# SCH_led_transistor_2026-04-28.net
KiCad netlist of a schematic drawn in EasyEDA
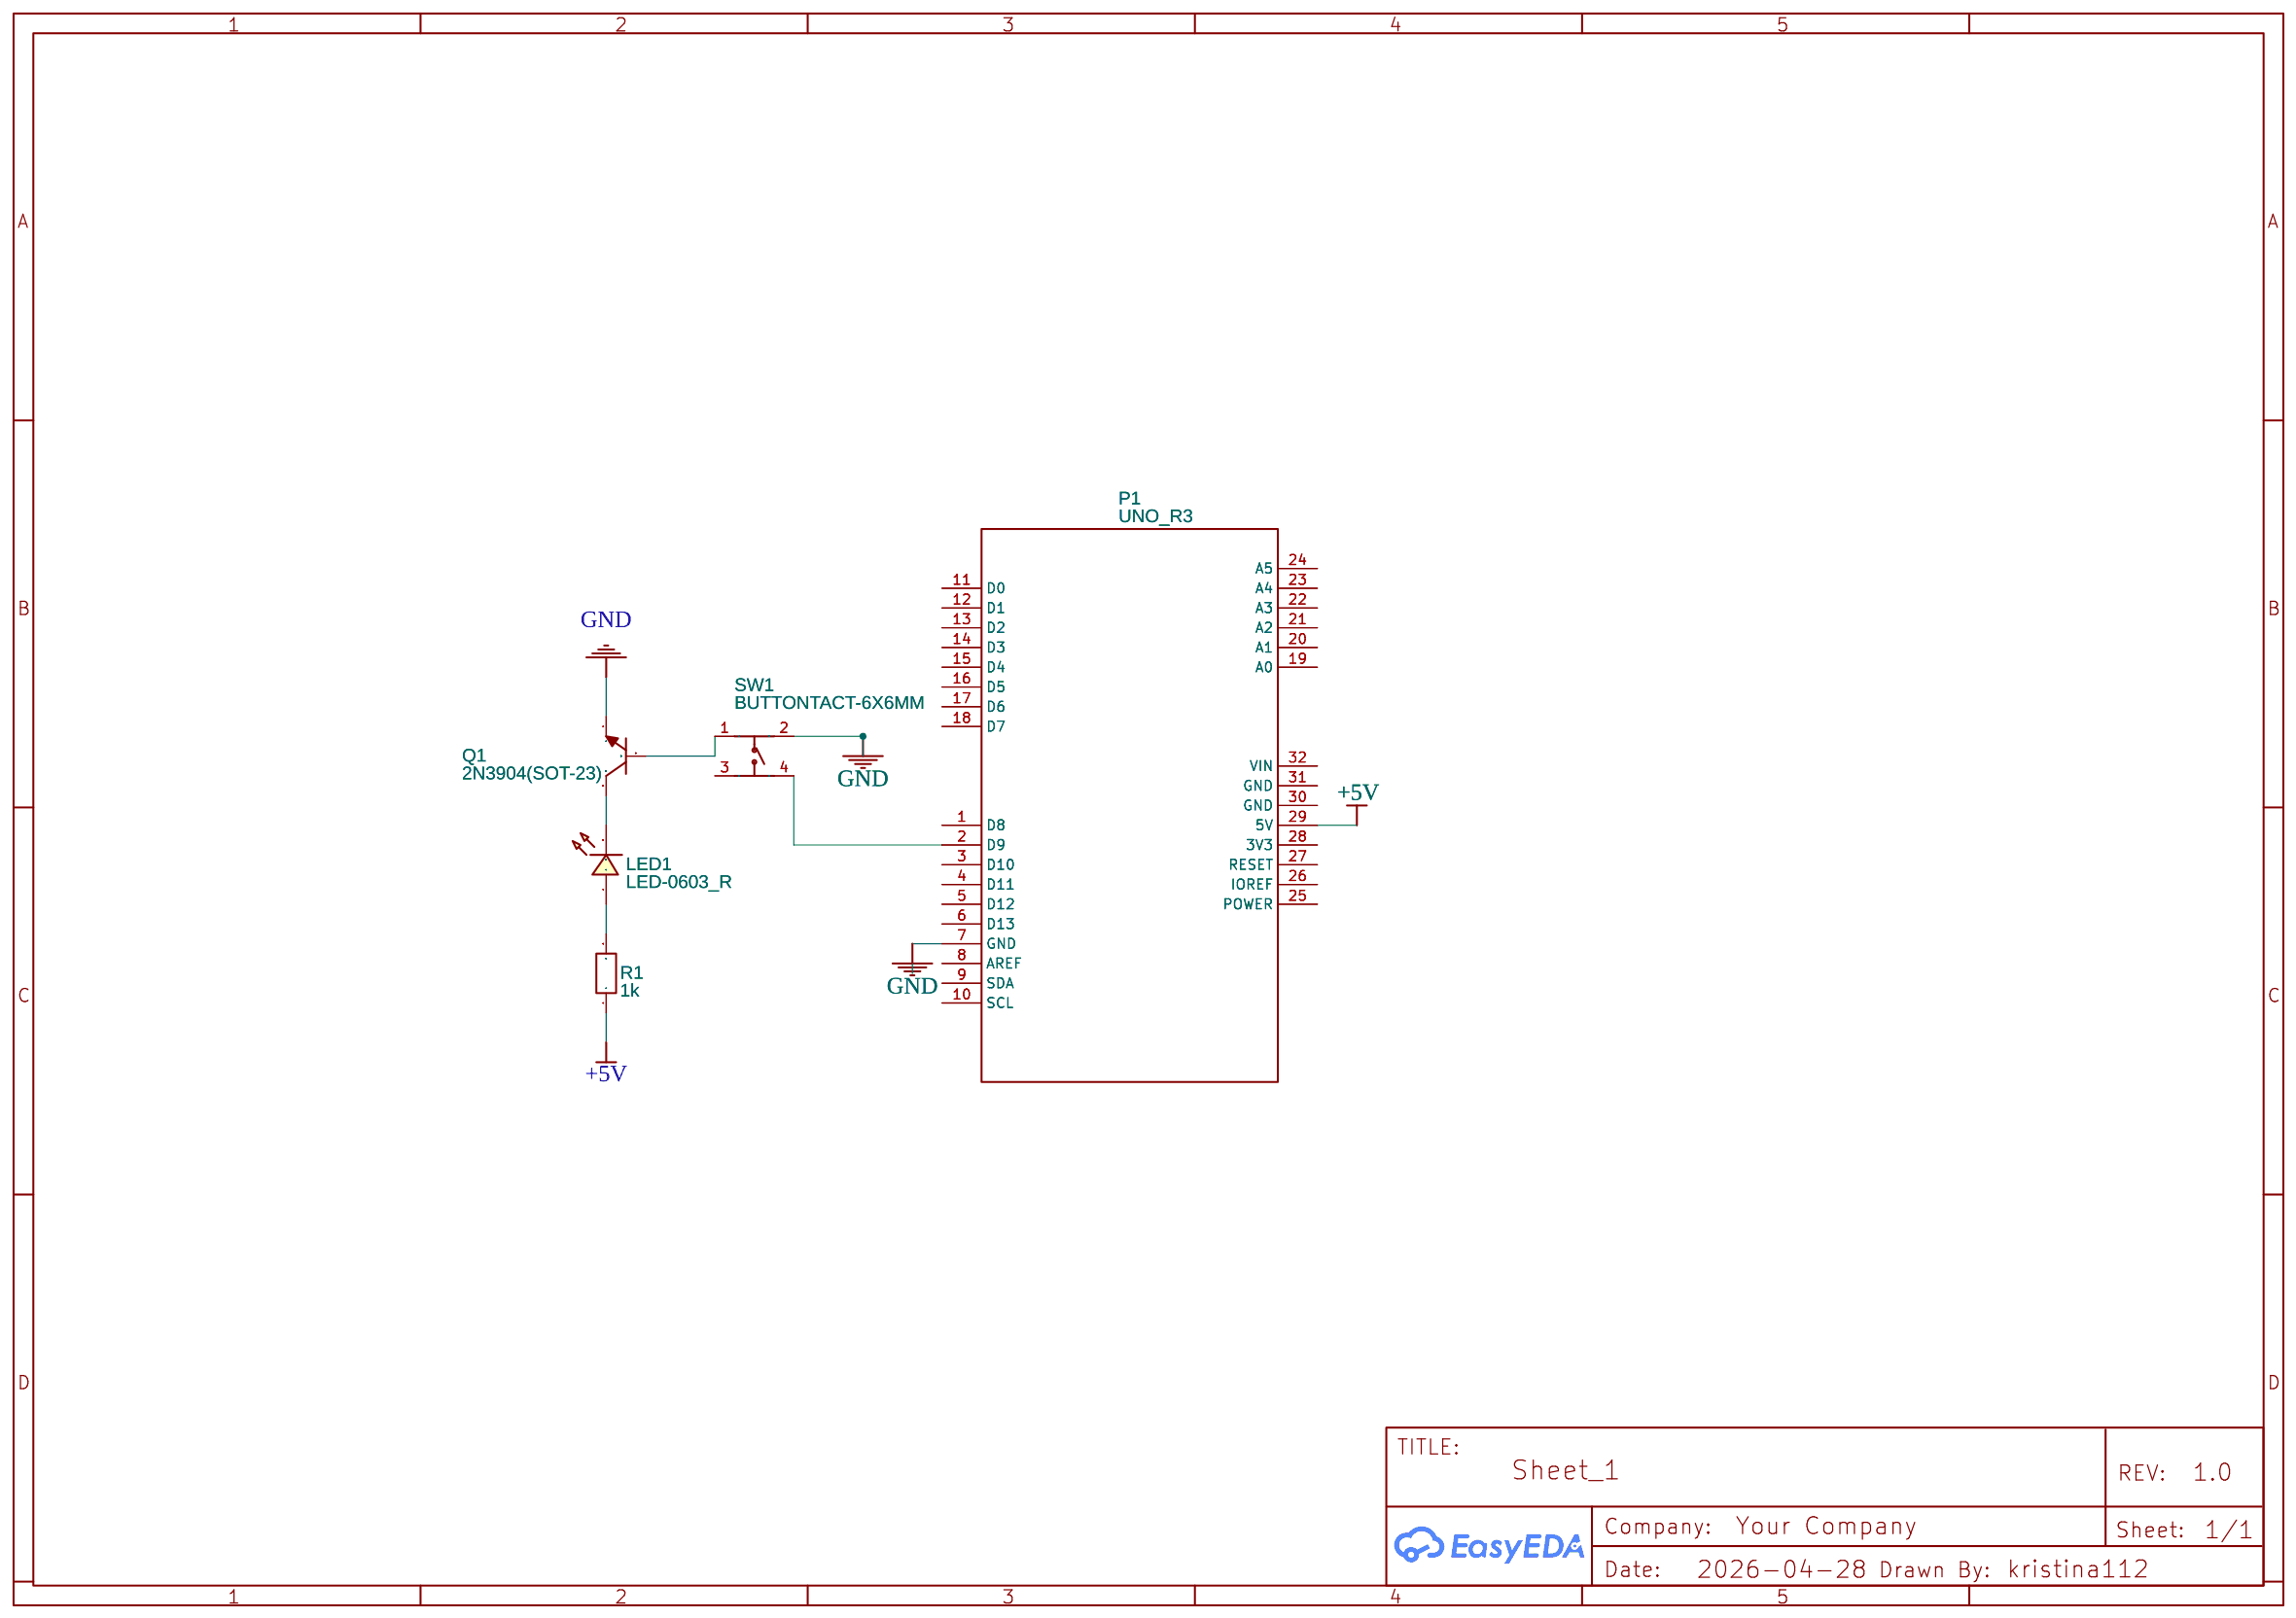
[diagram p0: schematic sheet]

(export (version "E")
  (design (tool "Eeschema 10.0.6"))
  (components
    (comp (ref "LED1")
      (value "LED-0603_R")
      (fields
        (field (name "Manufacturer Part") "19-217/R6C-AL1M2VY/3T")
        (field (name "Manufacturer") "EVERLIGHT(台湾亿光)")
      )
      (libsource (lib "") (part "LED-0603_R"))
    )
    (comp (ref "P1") (value "UNO_R3") (libsource (lib "") (part "UNO_R3")))
    (comp (ref "Q1")
      (value "2N3904(SOT-23)")
      (fields (field (name "Manufacturer Part") "2n3904S-RTK/PS") (field (name "Manufacturer") "KEC"))
      (libsource (lib "") (part "2N3904(SOT-23)"))
    )
    (comp (ref "R1") (value "1k") (libsource (lib "") (part "R_0603_EU")))
    (comp (ref "SW1")
      (value "BUTTONTACT-6X6MM")
      (fields (field (name "Manufacturer Part") "Buttontact-6x6mm"))
      (libsource (lib "") (part "BUTTONTACT-6X6MM"))
    )
  )
  (nets
    (net (code "1") (name "+5V") (class "Default")
      (node (ref "P1") (pin "29") (pinfunction "5V_29") (pintype "unspecified"))
      (node (ref "R1") (pin "1") (pinfunction "1_1") (pintype "unspecified"))
    )
    (net (code "2") (name "GND") (class "Default")
      (node (ref "P1") (pin "7") (pinfunction "GND_7") (pintype "unspecified"))
      (node (ref "Q1") (pin "1") (pinfunction "E_1") (pintype "input"))
      (node (ref "SW1") (pin "2") (pinfunction "B_2") (pintype "unspecified"))
    )
    (net (code "3") (name "Net-(LED1-Pad1)") (class "Default")
      (node (ref "LED1") (pin "1") (pinfunction "1_1") (pintype "unspecified"))
      (node (ref "R1") (pin "2") (pinfunction "2_2") (pintype "unspecified"))
    )
    (net (code "4") (name "Net-(P1-D9)") (class "Default")
      (node (ref "P1") (pin "2") (pinfunction "D9_2") (pintype "unspecified"))
      (node (ref "SW1") (pin "4") (pinfunction "D_4") (pintype "unspecified"))
    )
    (net (code "5") (name "Net-(Q1-B)") (class "Default")
      (node (ref "Q1") (pin "2") (pinfunction "B_2") (pintype "input"))
      (node (ref "SW1") (pin "1") (pinfunction "A_1") (pintype "unspecified"))
    )
    (net (code "6") (name "Net-(Q1-C)") (class "Default")
      (node (ref "LED1") (pin "2") (pinfunction "2_2") (pintype "unspecified"))
      (node (ref "Q1") (pin "3") (pinfunction "C_3") (pintype "input"))
    )
    (net (code "7") (name "unconnected-(P1-3V3-Pad28)") (class "Default")
      (node (ref "P1") (pin "28") (pinfunction "3V3_28") (pintype "unspecified"))
    )
    (net (code "8") (name "unconnected-(P1-A0-Pad19)") (class "Default")
      (node (ref "P1") (pin "19") (pinfunction "A0_19") (pintype "unspecified"))
    )
    (net (code "9") (name "unconnected-(P1-A1-Pad20)") (class "Default")
      (node (ref "P1") (pin "20") (pinfunction "A1_20") (pintype "unspecified"))
    )
    (net (code "10") (name "unconnected-(P1-A2-Pad21)") (class "Default")
      (node (ref "P1") (pin "21") (pinfunction "A2_21") (pintype "unspecified"))
    )
    (net (code "11") (name "unconnected-(P1-A3-Pad22)") (class "Default")
      (node (ref "P1") (pin "22") (pinfunction "A3_22") (pintype "unspecified"))
    )
    (net (code "12") (name "unconnected-(P1-A4-Pad23)") (class "Default")
      (node (ref "P1") (pin "23") (pinfunction "A4_23") (pintype "unspecified"))
    )
    (net (code "13") (name "unconnected-(P1-A5-Pad24)") (class "Default")
      (node (ref "P1") (pin "24") (pinfunction "A5_24") (pintype "unspecified"))
    )
    (net (code "14") (name "unconnected-(P1-AREF-Pad8)") (class "Default")
      (node (ref "P1") (pin "8") (pinfunction "AREF_8") (pintype "unspecified"))
    )
    (net (code "15") (name "unconnected-(P1-D0-Pad11)") (class "Default")
      (node (ref "P1") (pin "11") (pinfunction "D0_11") (pintype "unspecified"))
    )
    (net (code "16") (name "unconnected-(P1-D1-Pad12)") (class "Default")
      (node (ref "P1") (pin "12") (pinfunction "D1_12") (pintype "unspecified"))
    )
    (net (code "17") (name "unconnected-(P1-D2-Pad13)") (class "Default")
      (node (ref "P1") (pin "13") (pinfunction "D2_13") (pintype "unspecified"))
    )
    (net (code "18") (name "unconnected-(P1-D3-Pad14)") (class "Default")
      (node (ref "P1") (pin "14") (pinfunction "D3_14") (pintype "unspecified"))
    )
    (net (code "19") (name "unconnected-(P1-D4-Pad15)") (class "Default")
      (node (ref "P1") (pin "15") (pinfunction "D4_15") (pintype "unspecified"))
    )
    (net (code "20") (name "unconnected-(P1-D5-Pad16)") (class "Default")
      (node (ref "P1") (pin "16") (pinfunction "D5_16") (pintype "unspecified"))
    )
    (net (code "21") (name "unconnected-(P1-D6-Pad17)") (class "Default")
      (node (ref "P1") (pin "17") (pinfunction "D6_17") (pintype "unspecified"))
    )
    (net (code "22") (name "unconnected-(P1-D7-Pad18)") (class "Default")
      (node (ref "P1") (pin "18") (pinfunction "D7_18") (pintype "unspecified"))
    )
    (net (code "23") (name "unconnected-(P1-D8-Pad1)") (class "Default")
      (node (ref "P1") (pin "1") (pinfunction "D8_1") (pintype "unspecified"))
    )
    (net (code "24") (name "unconnected-(P1-D10-Pad3)") (class "Default")
      (node (ref "P1") (pin "3") (pinfunction "D10_3") (pintype "unspecified"))
    )
    (net (code "25") (name "unconnected-(P1-D11-Pad4)") (class "Default")
      (node (ref "P1") (pin "4") (pinfunction "D11_4") (pintype "unspecified"))
    )
    (net (code "26") (name "unconnected-(P1-D12-Pad5)") (class "Default")
      (node (ref "P1") (pin "5") (pinfunction "D12_5") (pintype "unspecified"))
    )
    (net (code "27") (name "unconnected-(P1-D13-Pad6)") (class "Default")
      (node (ref "P1") (pin "6") (pinfunction "D13_6") (pintype "unspecified"))
    )
    (net (code "28") (name "unconnected-(P1-GND-Pad30)") (class "Default")
      (node (ref "P1") (pin "30") (pinfunction "GND_30") (pintype "unspecified"))
    )
    (net (code "29") (name "unconnected-(P1-GND-Pad31)") (class "Default")
      (node (ref "P1") (pin "31") (pinfunction "GND_31") (pintype "unspecified"))
    )
    (net (code "30") (name "unconnected-(P1-IOREF-Pad26)") (class "Default")
      (node (ref "P1") (pin "26") (pinfunction "IOREF_26") (pintype "unspecified"))
    )
    (net (code "31") (name "unconnected-(P1-POWER-Pad25)") (class "Default")
      (node (ref "P1") (pin "25") (pinfunction "POWER_25") (pintype "unspecified"))
    )
    (net (code "32") (name "unconnected-(P1-RESET-Pad27)") (class "Default")
      (node (ref "P1") (pin "27") (pinfunction "RESET_27") (pintype "unspecified"))
    )
    (net (code "33") (name "unconnected-(P1-SCL-Pad10)") (class "Default")
      (node (ref "P1") (pin "10") (pinfunction "SCL_10") (pintype "unspecified"))
    )
    (net (code "34") (name "unconnected-(P1-SDA-Pad9)") (class "Default")
      (node (ref "P1") (pin "9") (pinfunction "SDA_9") (pintype "unspecified"))
    )
    (net (code "35") (name "unconnected-(P1-VIN-Pad32)") (class "Default")
      (node (ref "P1") (pin "32") (pinfunction "VIN_32") (pintype "unspecified"))
    )
    (net (code "36") (name "unconnected-(SW1-C-Pad3)") (class "Default")
      (node (ref "SW1") (pin "3") (pinfunction "C_3") (pintype "unspecified"))
    )
  )
)
